# TFG_PSoC_SCHEMATIC.net
KiCad netlist of a schematic drawn in Altium Designer
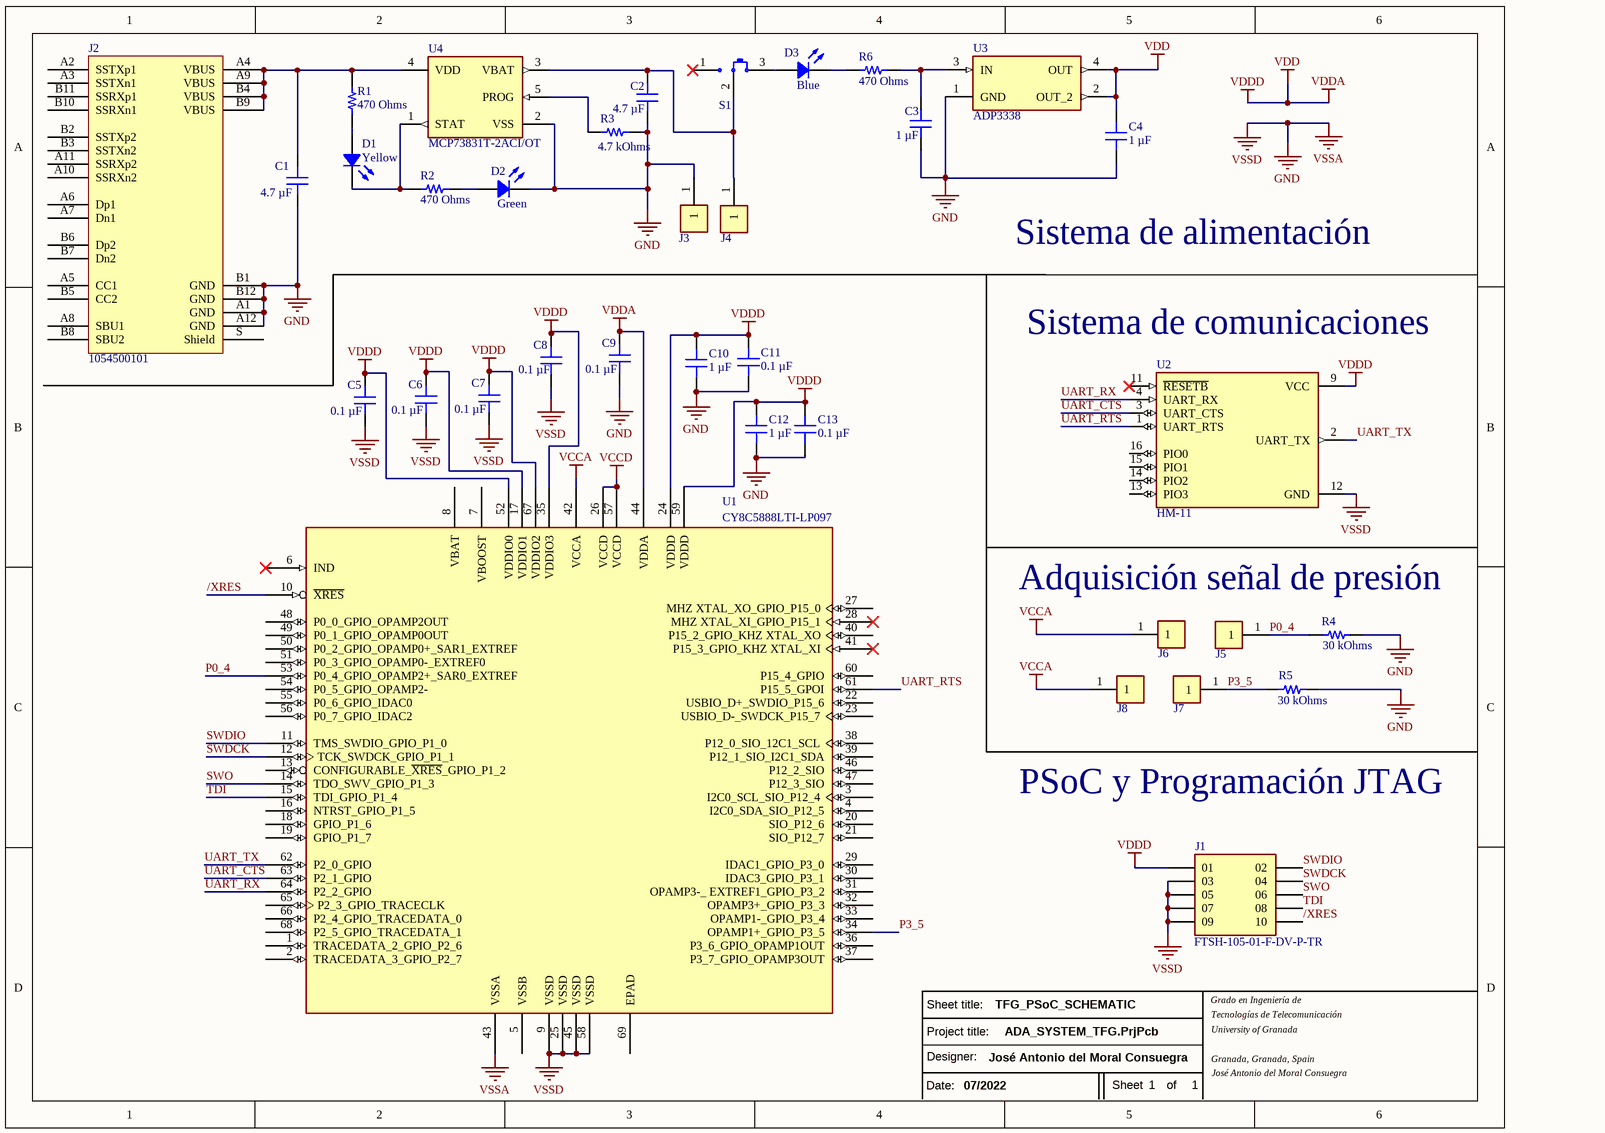
[diagram p0: TFG_PSoC_SCHEMATIC.SchDoc]

(export (version "E")
  (design (tool "Eeschema 10.0.6"))
  (components
    (comp (ref "C1")
      (value "4.7 µF")
      (footprint "CAP 0805_2012")
      (description "CAP CER 4.7UF 16V X7R 0805")
      (fields
        (field (name "PART NUMBER") "CL21B475KOFNFNE")
        (field (name "MANUFACTURER") "Samsung Electro-Mechanics")
      )
      (libsource (lib "Celestial Altium Library - altium_library") (part "Capacitor"))
    )
    (comp (ref "C2")
      (value "4.7 µF")
      (footprint "CAP 0805_2012")
      (description "CAP CER 4.7UF 16V X7R 0805")
      (fields
        (field (name "PART NUMBER") "CL21B475KOFNFNE")
        (field (name "MANUFACTURER") "Samsung Electro-Mechanics")
      )
      (libsource (lib "Celestial Altium Library - altium_library") (part "Capacitor"))
    )
    (comp (ref "C3")
      (value "1 µF")
      (footprint "CAP 0603_1608")
      (description "CAP CER 1UF 16V X7R 0603")
      (fields (field (name "PART NUMBER") "C0603X105M4RACAUTO") (field (name "MANUFACTURER") "KEMET"))
      (libsource (lib "Celestial Altium Library - altium_library") (part "Capacitor"))
    )
    (comp (ref "C4")
      (value "1 µF")
      (footprint "CAP 0603_1608")
      (description "CAP CER 1UF 16V X7R 0603")
      (fields (field (name "PART NUMBER") "C0603X105M4RACAUTO") (field (name "MANUFACTURER") "KEMET"))
      (libsource (lib "Celestial Altium Library - altium_library") (part "Capacitor"))
    )
    (comp (ref "C5")
      (value "0.1 µF")
      (footprint "CAP 0603_1608")
      (description "CAP CER 0.1UF 16V X7R 0603")
      (fields (field (name "PART NUMBER") "CS0603KRX7R7BB104") (field (name "MANUFACTURER") "Yageo"))
      (libsource (lib "Celestial Altium Library - altium_library") (part "Capacitor"))
    )
    (comp (ref "C6")
      (value "0.1 µF")
      (footprint "CAP 0603_1608")
      (description "CAP CER 0.1UF 16V X7R 0603")
      (fields (field (name "PART NUMBER") "CS0603KRX7R7BB104") (field (name "MANUFACTURER") "Yageo"))
      (libsource (lib "Celestial Altium Library - altium_library") (part "Capacitor"))
    )
    (comp (ref "C7")
      (value "0.1 µF")
      (footprint "CAP 0603_1608")
      (description "CAP CER 0.1UF 16V X7R 0603")
      (fields (field (name "PART NUMBER") "CS0603KRX7R7BB104") (field (name "MANUFACTURER") "Yageo"))
      (libsource (lib "Celestial Altium Library - altium_library") (part "Capacitor"))
    )
    (comp (ref "C8")
      (value "0.1 µF")
      (footprint "CAP 0603_1608")
      (description "CAP CER 0.1UF 16V X7R 0603")
      (fields (field (name "PART NUMBER") "CS0603KRX7R7BB104") (field (name "MANUFACTURER") "Yageo"))
      (libsource (lib "Celestial Altium Library - altium_library") (part "Capacitor"))
    )
    (comp (ref "C9")
      (value "0.1 µF")
      (footprint "CAP 0603_1608")
      (description "CAP CER 0.1UF 16V X7R 0603")
      (fields (field (name "PART NUMBER") "CS0603KRX7R7BB104") (field (name "MANUFACTURER") "Yageo"))
      (libsource (lib "Celestial Altium Library - altium_library") (part "Capacitor"))
    )
    (comp (ref "C10")
      (value "1 µF")
      (footprint "CAP 0603_1608")
      (description "CAP CER 1UF 16V X7R 0603")
      (fields (field (name "PART NUMBER") "C0603X105M4RACAUTO") (field (name "MANUFACTURER") "KEMET"))
      (libsource (lib "Celestial Altium Library - altium_library") (part "Capacitor"))
    )
    (comp (ref "C11")
      (value "0.1 µF")
      (footprint "CAP 0603_1608")
      (description "CAP CER 0.1UF 16V X7R 0603")
      (fields (field (name "PART NUMBER") "CS0603KRX7R7BB104") (field (name "MANUFACTURER") "Yageo"))
      (libsource (lib "Celestial Altium Library - altium_library") (part "Capacitor"))
    )
    (comp (ref "C12")
      (value "1 µF")
      (footprint "CAP 0603_1608")
      (description "CAP CER 1UF 16V X7R 0603")
      (fields (field (name "PART NUMBER") "C0603X105M4RACAUTO") (field (name "MANUFACTURER") "KEMET"))
      (libsource (lib "Celestial Altium Library - altium_library") (part "Capacitor"))
    )
    (comp (ref "C13")
      (value "0.1 µF")
      (footprint "CAP 0603_1608")
      (description "CAP CER 0.1UF 16V X7R 0603")
      (fields (field (name "PART NUMBER") "CS0603KRX7R7BB104") (field (name "MANUFACTURER") "Yageo"))
      (libsource (lib "Celestial Altium Library - altium_library") (part "Capacitor"))
    )
    (comp (ref "D1")
      (value "Yellow")
      (footprint "LED 1206_3216 YELLOW")
      (description "LED YELLOW 1206 SMD")
      (fields (field (name "PART NUMBER") "5990240007F") (field (name "MANUFACTURER") "Dialight"))
      (libsource (lib "Celestial Altium Library - altium_library") (part "LED"))
    )
    (comp (ref "D2")
      (value "Green")
      (footprint "LED 1206_3216 GREEN")
      (description "LED GREEN CLEAR 1206 SMD")
      (fields (field (name "PART NUMBER") "SM1206GC-IL") (field (name "MANUFACTURER") "Bivar Inc."))
      (libsource (lib "Celestial Altium Library - altium_library") (part "LED"))
    )
    (comp (ref "D3")
      (value "Blue")
      (footprint "LED 1206_3216 BLUE")
      (description "LED BLUE 1206 SMD")
      (fields (field (name "PART NUMBER") "5990291007F"))
      (libsource (lib "Celestial Altium Library - altium_library") (part "LED"))
    )
    (comp (ref "J1")
      (value "FTSH-105-01-F-DV-P-TR")
      (footprint "SAMTEC_FTSH-105-01-F-DV-P-TR")
      (fields (field (name "MF") "Samtec"))
      (libsource (lib "FTSH-105-01-F-DV-P-TR") (part "FTSH-105-01-F-DV-P-TR"))
    )
    (comp (ref "J2")
      (value "1054500101")
      (footprint "Molex 1054500101")
      (description "CONN RCP USB3.1 TYPEC 24P SMD RA")
      (fields (field (name "MANUFACTURER") "Molex"))
      (libsource (lib "Celestial Altium Library - altium_library") (part "USB 3.0 Type C"))
    )
    (comp (ref "J3")
      (value "103321-1")
      (footprint "TE_103321-1:TE_103321-1")
      (description "Pin 01 MODII HDR SRST B/A .100CL 1 POS")
      (fields (field (name "MF") "TE Connectivity"))
      (libsource (lib "103321-1") (part "103321-1"))
    )
    (comp (ref "J4")
      (value "103321-1")
      (footprint "TE_103321-1:TE_103321-1")
      (description "Pin 01 MODII HDR SRST B/A .100CL 1 POS")
      (fields (field (name "MF") "TE Connectivity"))
      (libsource (lib "103321-1") (part "103321-1"))
    )
    (comp (ref "J5")
      (value "103321-1")
      (footprint "TE_103321-1:TE_103321-1")
      (description "Pin 01 MODII HDR SRST B/A .100CL 1 POS")
      (fields (field (name "MF") "TE Connectivity"))
      (libsource (lib "") (part "103321-1_1"))
    )
    (comp (ref "J6")
      (value "103321-1")
      (footprint "TE_103321-1:TE_103321-1")
      (description "Pin 01 MODII HDR SRST B/A .100CL 1 POS")
      (fields (field (name "MF") "TE Connectivity"))
      (libsource (lib "") (part "103321-1_2"))
    )
    (comp (ref "J7")
      (value "103321-1")
      (footprint "TE_103321-1:TE_103321-1")
      (description "Pin 01 MODII HDR SRST B/A .100CL 1 POS")
      (fields (field (name "MF") "TE Connectivity"))
      (libsource (lib "") (part "103321-1_1"))
    )
    (comp (ref "J8")
      (value "103321-1")
      (footprint "TE_103321-1:TE_103321-1")
      (description "Pin 01 MODII HDR SRST B/A .100CL 1 POS")
      (fields (field (name "MF") "TE Connectivity"))
      (libsource (lib "") (part "103321-1_2"))
    )
    (comp (ref "R1")
      (value "470 Ohms")
      (footprint "RES 0603_1608")
      (description "RES 220 OHM 0.1% 1/10W 0603")
      (fields
        (field (name "PART NUMBER") "RN73R1JTTD2200B25")
        (field (name "MANUFACTURER") "KOA Speer Electronics, Inc.")
      )
      (libsource (lib "Celestial Altium Library - altium_library") (part "Resistor"))
    )
    (comp (ref "R2")
      (value "470 Ohms")
      (footprint "RES 0603_1608")
      (description "RES 220 OHM 0.1% 1/10W 0603")
      (fields
        (field (name "PART NUMBER") "RN73R1JTTD2200B25")
        (field (name "MANUFACTURER") "KOA Speer Electronics, Inc.")
      )
      (libsource (lib "Celestial Altium Library - altium_library") (part "Resistor"))
    )
    (comp (ref "R3")
      (value "4.7 kOhms")
      (footprint "RES 0603_1608")
      (description "RES SMD 20K OHM 1% 1/10W 0603")
      (fields (field (name "PART NUMBER") "CR0603-FX-2002ELF") (field (name "MANUFACTURER") "Bourns Inc."))
      (libsource (lib "Celestial Altium Library - altium_library") (part "Resistor"))
    )
    (comp (ref "R4")
      (value "30 kOhms")
      (footprint "RES 0603_1608")
      (description "RES SMD 30K OHM 0.1% 1/10W 0603")
      (fields
        (field (name "PART NUMBER") "ERA-3AEB303V")
        (field (name "MANUFACTURER") "Panasonic Electronic Components")
      )
      (libsource (lib "Celestial Altium Library - altium_library") (part "Resistor"))
    )
    (comp (ref "R5")
      (value "30 kOhms")
      (footprint "RES 0603_1608")
      (description "RES SMD 30K OHM 0.1% 1/10W 0603")
      (fields
        (field (name "PART NUMBER") "ERA-3AEB303V")
        (field (name "MANUFACTURER") "Panasonic Electronic Components")
      )
      (libsource (lib "Celestial Altium Library - altium_library") (part "Resistor"))
    )
    (comp (ref "R6")
      (value "470 Ohms")
      (footprint "RES 0603_1608")
      (description "RES 220 OHM 0.1% 1/10W 0603")
      (fields
        (field (name "PART NUMBER") "RN73R1JTTD2200B25")
        (field (name "MANUFACTURER") "KOA Speer Electronics, Inc.")
      )
      (libsource (lib "Celestial Altium Library - altium_library") (part "Resistor"))
    )
    (comp (ref "S1")
      (value "SS312SAH4-R")
      (footprint "NKK SS312SAH4")
      (description "SWITCH SLIDE SPDT 0.4VA 28V")
      (fields (field (name "MANUFACTURER") "NKK Switches"))
      (libsource (lib "Celestial Altium Library - altium_library") (part "NKK SS312"))
    )
    (comp (ref "U1")
      (value "CY8C5888LTI-LP097")
      (footprint "CY8C5888LTI-LP097:QFN-68")
      (fields (field (name "PART NUMBER") "CY8C5868LTI-LP036"))
      (libsource (lib "CY8C5888LTI-LP097") (part "CY8C5888LTI-LP097"))
    )
    (comp (ref "U2")
      (value "HM-11")
      (footprint "SnapEDApcb:XCVR_317030001")
      (description "Bluetooth Bluetooth v4.0 Transceiver Module 2.4GHz Integrated, Trace Surface Mount")
      (fields (field (name "MF") "Seeed Technology") (field (name "MP") "317030001"))
      (libsource (lib "SnapEDAsch") (part "317030001"))
    )
    (comp (ref "U3")
      (value "ADP3338")
      (footprint "SOT230P700X180-4N:SOT230P700X180-4N")
      (description "Linear Voltage Regulator IC Positive Fixed 1 Output 1A SOT-223-3")
      (fields
        (field (name "MP") "ADP3338AKCZ-3.3-RL")
        (field (name "DIGI-KEY_PART_NUMBER") "ADP3338AKCZ-3.3-RLCT-ND")
      )
      (libsource (lib "ADP3338AKCZ-3.3-RL") (part "ADP3338AKCZ-3.3-RL"))
    )
    (comp (ref "U4")
      (value "MCP73831T-2ACI/OT")
      (footprint "SOT95P280X145-5N:SOT95P280X145-5N")
      (description "Charger IC Lithium Ion/Polymer SOT-23-5")
      (fields (field (name "MP") "MCP73831T-4ADI/OT") (field (name "MF") "Microchip"))
      (libsource (lib "MCP73831T-4ADI_OT") (part "MCP73831T-4ADI/OT"))
    )
  )
  (nets
    (net (code "1") (name "/P0_4") (class "Default")
      (node (ref "J5") (pin "1") (pinfunction "1_1") (pintype "passive"))
      (node (ref "R4") (pin "2") (pinfunction "2_2") (pintype "passive"))
      (node (ref "U1") (pin "53") (pinfunction "P0_4_GPIO_OPAMP2+_SAR0_EXTREF_53") (pintype "bidirectional"))
    )
    (net (code "2") (name "/P3_5") (class "Default")
      (node (ref "J7") (pin "1") (pinfunction "1_1") (pintype "passive"))
      (node (ref "R5") (pin "2") (pinfunction "2_2") (pintype "passive"))
      (node (ref "U1") (pin "34") (pinfunction "OPAMP1+_GPIO_P3_5_34") (pintype "bidirectional"))
    )
    (net (code "3") (name "/SWDCK") (class "Default")
      (node (ref "J1") (pin "04") (pinfunction "04_04") (pintype "passive"))
      (node (ref "U1") (pin "12") (pinfunction "TCK_SWDCK_GPIO_P1_1_12") (pintype "bidirectional"))
    )
    (net (code "4") (name "/SWDIO") (class "Default")
      (node (ref "J1") (pin "02") (pinfunction "02_02") (pintype "passive"))
      (node (ref "U1") (pin "11") (pinfunction "TMS_SWDIO_GPIO_P1_0_11") (pintype "bidirectional"))
    )
    (net (code "5") (name "/SWO") (class "Default")
      (node (ref "J1") (pin "06") (pinfunction "06_06") (pintype "passive"))
      (node (ref "U1") (pin "14") (pinfunction "TDO_SWV_GPIO_P1_3_14") (pintype "bidirectional"))
    )
    (net (code "6") (name "/TDI") (class "Default")
      (node (ref "J1") (pin "08") (pinfunction "08_08") (pintype "passive"))
      (node (ref "U1") (pin "15") (pinfunction "TDI_GPIO_P1_4_15") (pintype "bidirectional"))
    )
    (net (code "7") (name "/UART_CTS") (class "Default")
      (node (ref "U1") (pin "63") (pinfunction "P2_1_GPIO_63") (pintype "bidirectional"))
      (node (ref "U2") (pin "3") (pinfunction "UART_CTS_3") (pintype "bidirectional"))
    )
    (net (code "8") (name "/UART_RTS") (class "Default")
      (node (ref "U1") (pin "61") (pinfunction "P15_5_GPOI_61") (pintype "bidirectional"))
      (node (ref "U2") (pin "1") (pinfunction "UART_RTS_1") (pintype "bidirectional"))
    )
    (net (code "9") (name "/UART_RX") (class "Default")
      (node (ref "U1") (pin "64") (pinfunction "P2_2_GPIO_64") (pintype "bidirectional"))
      (node (ref "U2") (pin "4") (pinfunction "UART_RX_4") (pintype "input"))
    )
    (net (code "10") (name "/UART_TX") (class "Default")
      (node (ref "U1") (pin "62") (pinfunction "P2_0_GPIO_62") (pintype "bidirectional"))
      (node (ref "U2") (pin "2") (pinfunction "UART_TX_2") (pintype "output"))
    )
    (net (code "11") (name "/{slash}XRES") (class "Default")
      (node (ref "J1") (pin "10") (pinfunction "10_10") (pintype "passive"))
      (node (ref "U1") (pin "10") (pinfunction "~{XRES}_10") (pintype "input"))
    )
    (net (code "12") (name "GND") (class "Default")
      (node (ref "C1") (pin "1") (pinfunction "1_1") (pintype "passive"))
      (node (ref "C10") (pin "1") (pinfunction "1_1") (pintype "passive"))
      (node (ref "C11") (pin "1") (pinfunction "1_1") (pintype "passive"))
      (node (ref "C12") (pin "1") (pinfunction "1_1") (pintype "passive"))
      (node (ref "C13") (pin "1") (pinfunction "1_1") (pintype "passive"))
      (node (ref "C2") (pin "2") (pinfunction "2_2") (pintype "passive"))
      (node (ref "C3") (pin "1") (pinfunction "1_1") (pintype "passive"))
      (node (ref "C4") (pin "1") (pinfunction "1_1") (pintype "passive"))
      (node (ref "C5") (pin "1") (pinfunction "1_1") (pintype "passive"))
      (node (ref "C6") (pin "1") (pinfunction "1_1") (pintype "passive"))
      (node (ref "C7") (pin "1") (pinfunction "1_1") (pintype "passive"))
      (node (ref "C8") (pin "1") (pinfunction "1_1") (pintype "passive"))
      (node (ref "C9") (pin "1") (pinfunction "1_1") (pintype "passive"))
      (node (ref "D2") (pin "2") (pinfunction "2_2") (pintype "passive"))
      (node (ref "J1") (pin "03") (pinfunction "03_03") (pintype "passive"))
      (node (ref "J1") (pin "05") (pinfunction "05_05") (pintype "passive"))
      (node (ref "J1") (pin "07") (pinfunction "07_07") (pintype "passive"))
      (node (ref "J1") (pin "09") (pinfunction "09_09") (pintype "passive"))
      (node (ref "J2") (pin "A1") (pinfunction "GND_A1") (pintype "passive"))
      (node (ref "J2") (pin "A12") (pinfunction "GND_A12") (pintype "passive"))
      (node (ref "J2") (pin "B1") (pinfunction "GND_B1") (pintype "passive"))
      (node (ref "J2") (pin "B12") (pinfunction "GND_B12") (pintype "passive"))
      (node (ref "J3") (pin "1") (pinfunction "1_1") (pintype "passive"))
      (node (ref "R3") (pin "2") (pinfunction "2_2") (pintype "passive"))
      (node (ref "R4") (pin "1") (pinfunction "1_1") (pintype "passive"))
      (node (ref "R5") (pin "1") (pinfunction "1_1") (pintype "passive"))
      (node (ref "U1") (pin "25") (pinfunction "VSSD_25") (pintype "power_in"))
      (node (ref "U1") (pin "43") (pinfunction "VSSA_43") (pintype "power_in"))
      (node (ref "U1") (pin "45") (pinfunction "VSSD_45") (pintype "power_in"))
      (node (ref "U1") (pin "58") (pinfunction "VSSD_58") (pintype "power_in"))
      (node (ref "U1") (pin "9") (pinfunction "VSSD_9") (pintype "power_in"))
      (node (ref "U2") (pin "12") (pinfunction "GND_12") (pintype "power_in"))
      (node (ref "U3") (pin "1") (pinfunction "GND_1") (pintype "passive"))
      (node (ref "U4") (pin "2") (pinfunction "VSS_2") (pintype "power_in"))
    )
    (net (code "13") (name "Net-(D1-Pad1)") (class "Default")
      (node (ref "D1") (pin "1") (pinfunction "1_1") (pintype "passive"))
      (node (ref "R1") (pin "1") (pinfunction "1_1") (pintype "passive"))
    )
    (net (code "14") (name "Net-(D2-Pad1)") (class "Default")
      (node (ref "D2") (pin "1") (pinfunction "1_1") (pintype "passive"))
      (node (ref "R2") (pin "1") (pinfunction "1_1") (pintype "passive"))
    )
    (net (code "15") (name "Net-(D3-Pad1)") (class "Default")
      (node (ref "D3") (pin "1") (pinfunction "1_1") (pintype "passive"))
      (node (ref "S1") (pin "3") (pinfunction "3_3") (pintype "passive"))
    )
    (net (code "16") (name "Net-(D3-Pad2)") (class "Default")
      (node (ref "D3") (pin "2") (pinfunction "2_2") (pintype "passive"))
      (node (ref "R6") (pin "2") (pinfunction "2_2") (pintype "passive"))
    )
    (net (code "17") (name "Net-(S1-COM)") (class "Default")
      (node (ref "C2") (pin "1") (pinfunction "1_1") (pintype "passive"))
      (node (ref "J4") (pin "1") (pinfunction "1_1") (pintype "passive"))
      (node (ref "S1") (pin "2") (pinfunction "COM_2") (pintype "passive"))
      (node (ref "U4") (pin "3") (pinfunction "VBAT_3") (pintype "output"))
    )
    (net (code "18") (name "Net-(U3-IN)") (class "Default")
      (node (ref "C3") (pin "2") (pinfunction "2_2") (pintype "passive"))
      (node (ref "R6") (pin "1") (pinfunction "1_1") (pintype "passive"))
      (node (ref "U3") (pin "3") (pinfunction "IN_3") (pintype "input"))
    )
    (net (code "19") (name "Net-(U4-PROG)") (class "Default")
      (node (ref "R3") (pin "1") (pinfunction "1_1") (pintype "passive"))
      (node (ref "U4") (pin "5") (pinfunction "PROG_5") (pintype "input"))
    )
    (net (code "20") (name "Net-(U4-STAT)") (class "Default")
      (node (ref "D1") (pin "2") (pinfunction "2_2") (pintype "passive"))
      (node (ref "R2") (pin "2") (pinfunction "2_2") (pintype "passive"))
      (node (ref "U4") (pin "1") (pinfunction "STAT_1") (pintype "output"))
    )
    (net (code "21") (name "Net-(U4-VDD)") (class "Default")
      (node (ref "C1") (pin "2") (pinfunction "2_2") (pintype "passive"))
      (node (ref "J2") (pin "A4") (pinfunction "VBUS_A4") (pintype "passive"))
      (node (ref "J2") (pin "A9") (pinfunction "VBUS_A9") (pintype "passive"))
      (node (ref "J2") (pin "B4") (pinfunction "VBUS_B4") (pintype "passive"))
      (node (ref "J2") (pin "B9") (pinfunction "VBUS_B9") (pintype "passive"))
      (node (ref "R1") (pin "2") (pinfunction "2_2") (pintype "passive"))
      (node (ref "U4") (pin "4") (pinfunction "VDD_4") (pintype "power_in"))
    )
    (net (code "22") (name "VCCA") (class "Default")
      (node (ref "J6") (pin "1") (pinfunction "1_1") (pintype "passive"))
      (node (ref "J8") (pin "1") (pinfunction "1_1") (pintype "passive"))
      (node (ref "U1") (pin "42") (pinfunction "VCCA_42") (pintype "power_in"))
    )
    (net (code "23") (name "VCCD") (class "Default")
      (node (ref "U1") (pin "26") (pinfunction "VCCD_26") (pintype "power_in"))
      (node (ref "U1") (pin "57") (pinfunction "VCCD_57") (pintype "power_in"))
    )
    (net (code "24") (name "VDD") (class "Default")
      (node (ref "C10") (pin "2") (pinfunction "2_2") (pintype "passive"))
      (node (ref "C11") (pin "2") (pinfunction "2_2") (pintype "passive"))
      (node (ref "C12") (pin "2") (pinfunction "2_2") (pintype "passive"))
      (node (ref "C13") (pin "2") (pinfunction "2_2") (pintype "passive"))
      (node (ref "C4") (pin "2") (pinfunction "2_2") (pintype "passive"))
      (node (ref "C5") (pin "2") (pinfunction "2_2") (pintype "passive"))
      (node (ref "C6") (pin "2") (pinfunction "2_2") (pintype "passive"))
      (node (ref "C7") (pin "2") (pinfunction "2_2") (pintype "passive"))
      (node (ref "C8") (pin "2") (pinfunction "2_2") (pintype "passive"))
      (node (ref "C9") (pin "2") (pinfunction "2_2") (pintype "passive"))
      (node (ref "J1") (pin "01") (pinfunction "01_01") (pintype "passive"))
      (node (ref "U1") (pin "17") (pinfunction "VDDIO1_17") (pintype "power_in"))
      (node (ref "U1") (pin "24") (pinfunction "VDDD_24") (pintype "power_in"))
      (node (ref "U1") (pin "35") (pinfunction "VDDIO3_35") (pintype "power_in"))
      (node (ref "U1") (pin "44") (pinfunction "VDDA_44") (pintype "power_in"))
      (node (ref "U1") (pin "52") (pinfunction "VDDIO0_52") (pintype "power_in"))
      (node (ref "U1") (pin "59") (pinfunction "VDDD_59") (pintype "power_in"))
      (node (ref "U1") (pin "67") (pinfunction "VDDIO2_67") (pintype "power_in"))
      (node (ref "U2") (pin "9") (pinfunction "VCC_9") (pintype "power_in"))
      (node (ref "U3") (pin "2") (pinfunction "OUT_2_2") (pintype "output"))
      (node (ref "U3") (pin "4") (pinfunction "OUT_4") (pintype "output"))
    )
    (net (code "25") (name "unconnected-(J2-CC1-PadA5)") (class "Default")
      (node (ref "J2") (pin "A5") (pinfunction "CC1_A5") (pintype "passive"))
    )
    (net (code "26") (name "unconnected-(J2-CC2-PadB5)") (class "Default")
      (node (ref "J2") (pin "B5") (pinfunction "CC2_B5") (pintype "passive"))
    )
    (net (code "27") (name "unconnected-(J2-Dn1-PadA7)") (class "Default")
      (node (ref "J2") (pin "A7") (pinfunction "Dn1_A7") (pintype "passive"))
    )
    (net (code "28") (name "unconnected-(J2-Dn2-PadB7)") (class "Default")
      (node (ref "J2") (pin "B7") (pinfunction "Dn2_B7") (pintype "passive"))
    )
    (net (code "29") (name "unconnected-(J2-Dp1-PadA6)") (class "Default")
      (node (ref "J2") (pin "A6") (pinfunction "Dp1_A6") (pintype "passive"))
    )
    (net (code "30") (name "unconnected-(J2-Dp2-PadB6)") (class "Default")
      (node (ref "J2") (pin "B6") (pinfunction "Dp2_B6") (pintype "passive"))
    )
    (net (code "31") (name "unconnected-(J2-SBU1-PadA8)") (class "Default")
      (node (ref "J2") (pin "A8") (pinfunction "SBU1_A8") (pintype "passive"))
    )
    (net (code "32") (name "unconnected-(J2-SBU2-PadB8)") (class "Default")
      (node (ref "J2") (pin "B8") (pinfunction "SBU2_B8") (pintype "passive"))
    )
    (net (code "33") (name "unconnected-(J2-SSRXn1-PadB10)") (class "Default")
      (node (ref "J2") (pin "B10") (pinfunction "SSRXn1_B10") (pintype "passive"))
    )
    (net (code "34") (name "unconnected-(J2-SSRXn2-PadA10)") (class "Default")
      (node (ref "J2") (pin "A10") (pinfunction "SSRXn2_A10") (pintype "passive"))
    )
    (net (code "35") (name "unconnected-(J2-SSRXp1-PadB11)") (class "Default")
      (node (ref "J2") (pin "B11") (pinfunction "SSRXp1_B11") (pintype "passive"))
    )
    (net (code "36") (name "unconnected-(J2-SSRXp2-PadA11)") (class "Default")
      (node (ref "J2") (pin "A11") (pinfunction "SSRXp2_A11") (pintype "passive"))
    )
    (net (code "37") (name "unconnected-(J2-SSTXn1-PadA3)") (class "Default")
      (node (ref "J2") (pin "A3") (pinfunction "SSTXn1_A3") (pintype "passive"))
    )
    (net (code "38") (name "unconnected-(J2-SSTXn2-PadB3)") (class "Default")
      (node (ref "J2") (pin "B3") (pinfunction "SSTXn2_B3") (pintype "passive"))
    )
    (net (code "39") (name "unconnected-(J2-SSTXp1-PadA2)") (class "Default")
      (node (ref "J2") (pin "A2") (pinfunction "SSTXp1_A2") (pintype "passive"))
    )
    (net (code "40") (name "unconnected-(J2-SSTXp2-PadB2)") (class "Default")
      (node (ref "J2") (pin "B2") (pinfunction "SSTXp2_B2") (pintype "passive"))
    )
    (net (code "41") (name "unconnected-(J2-Shield-PadS)") (class "Default")
      (node (ref "J2") (pin "S") (pinfunction "Shield_S") (pintype "passive"))
    )
    (net (code "42") (name "unconnected-(S1-Pad1)") (class "Default")
      (node (ref "S1") (pin "1") (pinfunction "1_1") (pintype "passive+no_connect"))
    )
    (net (code "43") (name "unconnected-(U1-CONFIGURABLE_~{XRES}_GPIO_P1_2-Pad13)") (class "Default")
      (node (ref "U1") (pin "13") (pinfunction "CONFIGURABLE_~{XRES}_GPIO_P1_2_13") (pintype "bidirectional"))
    )
    (net (code "44") (name "unconnected-(U1-EPAD-Pad69)") (class "Default")
      (node (ref "U1") (pin "69") (pinfunction "EPAD_69") (pintype "power_in"))
    )
    (net (code "45") (name "unconnected-(U1-GPIO_P1_6-Pad18)") (class "Default")
      (node (ref "U1") (pin "18") (pinfunction "GPIO_P1_6_18") (pintype "bidirectional"))
    )
    (net (code "46") (name "unconnected-(U1-GPIO_P1_7-Pad19)") (class "Default")
      (node (ref "U1") (pin "19") (pinfunction "GPIO_P1_7_19") (pintype "bidirectional"))
    )
    (net (code "47") (name "unconnected-(U1-I2C0_SCL_SIO_P12_4-Pad3)") (class "Default")
      (node (ref "U1") (pin "3") (pinfunction "I2C0_SCL_SIO_P12_4_3") (pintype "bidirectional"))
    )
    (net (code "48") (name "unconnected-(U1-I2C0_SDA_SIO_P12_5-Pad4)") (class "Default")
      (node (ref "U1") (pin "4") (pinfunction "I2C0_SDA_SIO_P12_5_4") (pintype "bidirectional"))
    )
    (net (code "49") (name "unconnected-(U1-IDAC1_GPIO_P3_0-Pad29)") (class "Default")
      (node (ref "U1") (pin "29") (pinfunction "IDAC1_GPIO_P3_0_29") (pintype "bidirectional"))
    )
    (net (code "50") (name "unconnected-(U1-IDAC3_GPIO_P3_1-Pad30)") (class "Default")
      (node (ref "U1") (pin "30") (pinfunction "IDAC3_GPIO_P3_1_30") (pintype "bidirectional"))
    )
    (net (code "51") (name "unconnected-(U1-IND-Pad6)") (class "Default")
      (node (ref "U1") (pin "6") (pinfunction "IND_6") (pintype "input+no_connect"))
    )
    (net (code "52") (name "unconnected-(U1-MHZ_XTAL_XI_GPIO_P15_1-Pad28)") (class "Default")
      (node (ref "U1") (pin "28") (pinfunction "MHZ_XTAL_XI_GPIO_P15_1_28") (pintype "input+no_connect"))
    )
    (net (code "53") (name "unconnected-(U1-MHZ_XTAL_XO_GPIO_P15_0-Pad27)") (class "Default")
      (node (ref "U1") (pin "27") (pinfunction "MHZ_XTAL_XO_GPIO_P15_0_27") (pintype "bidirectional"))
    )
    (net (code "54") (name "unconnected-(U1-NTRST_GPIO_P1_5-Pad16)") (class "Default")
      (node (ref "U1") (pin "16") (pinfunction "NTRST_GPIO_P1_5_16") (pintype "bidirectional"))
    )
    (net (code "55") (name "unconnected-(U1-OPAMP1-_GPIO_P3_4-Pad33)") (class "Default")
      (node (ref "U1") (pin "33") (pinfunction "OPAMP1-_GPIO_P3_4_33") (pintype "bidirectional"))
    )
    (net (code "56") (name "unconnected-(U1-OPAMP3+_GPIO_P3_3-Pad32)") (class "Default")
      (node (ref "U1") (pin "32") (pinfunction "OPAMP3+_GPIO_P3_3_32") (pintype "bidirectional"))
    )
    (net (code "57") (name "unconnected-(U1-OPAMP3-__EXTREF1_GPIO_P3_2-Pad31)") (class "Default")
      (node (ref "U1") (pin "31") (pinfunction "OPAMP3-__EXTREF1_GPIO_P3_2_31") (pintype "bidirectional"))
    )
    (net (code "58") (name "unconnected-(U1-P0_0_GPIO_OPAMP2OUT-Pad48)") (class "Default")
      (node (ref "U1") (pin "48") (pinfunction "P0_0_GPIO_OPAMP2OUT_48") (pintype "bidirectional"))
    )
    (net (code "59") (name "unconnected-(U1-P0_1_GPIO_OPAMP0OUT-Pad49)") (class "Default")
      (node (ref "U1") (pin "49") (pinfunction "P0_1_GPIO_OPAMP0OUT_49") (pintype "bidirectional"))
    )
    (net (code "60") (name "unconnected-(U1-P0_2_GPIO_OPAMP0+_SAR1_EXTREF-Pad50)") (class "Default")
      (node (ref "U1") (pin "50") (pinfunction "P0_2_GPIO_OPAMP0+_SAR1_EXTREF_50") (pintype "bidirectional"))
    )
    (net (code "61") (name "unconnected-(U1-P0_3_GPIO_OPAMP0-_EXTREF0-Pad51)") (class "Default")
      (node (ref "U1") (pin "51") (pinfunction "P0_3_GPIO_OPAMP0-_EXTREF0_51") (pintype "bidirectional"))
    )
    (net (code "62") (name "unconnected-(U1-P0_5_GPIO_OPAMP2--Pad54)") (class "Default")
      (node (ref "U1") (pin "54") (pinfunction "P0_5_GPIO_OPAMP2-_54") (pintype "bidirectional"))
    )
    (net (code "63") (name "unconnected-(U1-P0_6_GPIO_IDAC0-Pad55)") (class "Default")
      (node (ref "U1") (pin "55") (pinfunction "P0_6_GPIO_IDAC0_55") (pintype "bidirectional"))
    )
    (net (code "64") (name "unconnected-(U1-P0_7_GPIO_IDAC2-Pad56)") (class "Default")
      (node (ref "U1") (pin "56") (pinfunction "P0_7_GPIO_IDAC2_56") (pintype "bidirectional"))
    )
    (net (code "65") (name "unconnected-(U1-P2_3_GPIO_TRACECLK-Pad65)") (class "Default")
      (node (ref "U1") (pin "65") (pinfunction "P2_3_GPIO_TRACECLK_65") (pintype "bidirectional"))
    )
    (net (code "66") (name "unconnected-(U1-P2_4_GPIO_TRACEDATA_0-Pad66)") (class "Default")
      (node (ref "U1") (pin "66") (pinfunction "P2_4_GPIO_TRACEDATA_0_66") (pintype "bidirectional"))
    )
    (net (code "67") (name "unconnected-(U1-P2_5_GPIO_TRACEDATA_1-Pad68)") (class "Default")
      (node (ref "U1") (pin "68") (pinfunction "P2_5_GPIO_TRACEDATA_1_68") (pintype "bidirectional"))
    )
    (net (code "68") (name "unconnected-(U1-P3_6_GPIO_OPAMP1OUT-Pad36)") (class "Default")
      (node (ref "U1") (pin "36") (pinfunction "P3_6_GPIO_OPAMP1OUT_36") (pintype "bidirectional"))
    )
    (net (code "69") (name "unconnected-(U1-P3_7_GPIO_OPAMP3OUT-Pad37)") (class "Default")
      (node (ref "U1") (pin "37") (pinfunction "P3_7_GPIO_OPAMP3OUT_37") (pintype "bidirectional"))
    )
    (net (code "70") (name "unconnected-(U1-P12_0_SIO_12C1_SCL-Pad38)") (class "Default")
      (node (ref "U1") (pin "38") (pinfunction "P12_0_SIO_12C1_SCL_38") (pintype "bidirectional"))
    )
    (net (code "71") (name "unconnected-(U1-P12_1_SIO_I2C1_SDA-Pad39)") (class "Default")
      (node (ref "U1") (pin "39") (pinfunction "P12_1_SIO_I2C1_SDA_39") (pintype "bidirectional"))
    )
    (net (code "72") (name "unconnected-(U1-P12_2_SIO-Pad46)") (class "Default")
      (node (ref "U1") (pin "46") (pinfunction "P12_2_SIO_46") (pintype "bidirectional"))
    )
    (net (code "73") (name "unconnected-(U1-P12_3_SIO-Pad47)") (class "Default")
      (node (ref "U1") (pin "47") (pinfunction "P12_3_SIO_47") (pintype "bidirectional"))
    )
    (net (code "74") (name "unconnected-(U1-P15_2_GPIO_KHZ_XTAL_XO-Pad40)") (class "Default")
      (node (ref "U1") (pin "40") (pinfunction "P15_2_GPIO_KHZ_XTAL_XO_40") (pintype "bidirectional"))
    )
    (net (code "75") (name "unconnected-(U1-P15_3_GPIO_KHZ_XTAL_XI-Pad41)") (class "Default")
      (node (ref "U1") (pin "41") (pinfunction "P15_3_GPIO_KHZ_XTAL_XI_41") (pintype "input+no_connect"))
    )
    (net (code "76") (name "unconnected-(U1-P15_4_GPIO-Pad60)") (class "Default")
      (node (ref "U1") (pin "60") (pinfunction "P15_4_GPIO_60") (pintype "bidirectional"))
    )
    (net (code "77") (name "unconnected-(U1-SIO_P12_6-Pad20)") (class "Default")
      (node (ref "U1") (pin "20") (pinfunction "SIO_P12_6_20") (pintype "bidirectional"))
    )
    (net (code "78") (name "unconnected-(U1-SIO_P12_7-Pad21)") (class "Default")
      (node (ref "U1") (pin "21") (pinfunction "SIO_P12_7_21") (pintype "bidirectional"))
    )
    (net (code "79") (name "unconnected-(U1-TRACEDATA_2_GPIO_P2_6-Pad1)") (class "Default")
      (node (ref "U1") (pin "1") (pinfunction "TRACEDATA_2_GPIO_P2_6_1") (pintype "bidirectional"))
    )
    (net (code "80") (name "unconnected-(U1-TRACEDATA_3_GPIO_P2_7-Pad2)") (class "Default")
      (node (ref "U1") (pin "2") (pinfunction "TRACEDATA_3_GPIO_P2_7_2") (pintype "bidirectional"))
    )
    (net (code "81") (name "unconnected-(U1-USBIO_D+_SWDIO_P15_6-Pad22)") (class "Default")
      (node (ref "U1") (pin "22") (pinfunction "USBIO_D+_SWDIO_P15_6_22") (pintype "bidirectional"))
    )
    (net (code "82") (name "unconnected-(U1-USBIO_D-_SWDCK_P15_7-Pad23)") (class "Default")
      (node (ref "U1") (pin "23") (pinfunction "USBIO_D-_SWDCK_P15_7_23") (pintype "bidirectional"))
    )
    (net (code "83") (name "unconnected-(U1-VBAT-Pad8)") (class "Default")
      (node (ref "U1") (pin "8") (pinfunction "VBAT_8") (pintype "power_in"))
    )
    (net (code "84") (name "unconnected-(U1-VBOOST-Pad7)") (class "Default")
      (node (ref "U1") (pin "7") (pinfunction "VBOOST_7") (pintype "power_in"))
    )
    (net (code "85") (name "unconnected-(U1-VSSB-Pad5)") (class "Default")
      (node (ref "U1") (pin "5") (pinfunction "VSSB_5") (pintype "power_in"))
    )
    (net (code "86") (name "unconnected-(U2-PIO0-Pad16)") (class "Default")
      (node (ref "U2") (pin "16") (pinfunction "PIO0_16") (pintype "bidirectional"))
    )
    (net (code "87") (name "unconnected-(U2-PIO1-Pad15)") (class "Default")
      (node (ref "U2") (pin "15") (pinfunction "PIO1_15") (pintype "bidirectional"))
    )
    (net (code "88") (name "unconnected-(U2-PIO2-Pad14)") (class "Default")
      (node (ref "U2") (pin "14") (pinfunction "PIO2_14") (pintype "bidirectional"))
    )
    (net (code "89") (name "unconnected-(U2-PIO3-Pad13)") (class "Default")
      (node (ref "U2") (pin "13") (pinfunction "PIO3_13") (pintype "bidirectional"))
    )
    (net (code "90") (name "unconnected-(U2-~{RESETB}-Pad11)") (class "Default")
      (node (ref "U2") (pin "11") (pinfunction "~{RESETB}_11") (pintype "input+no_connect"))
    )
  )
)
